# wifi_radio.net
KiCad netlist of a schematic drawn in Altium Designer
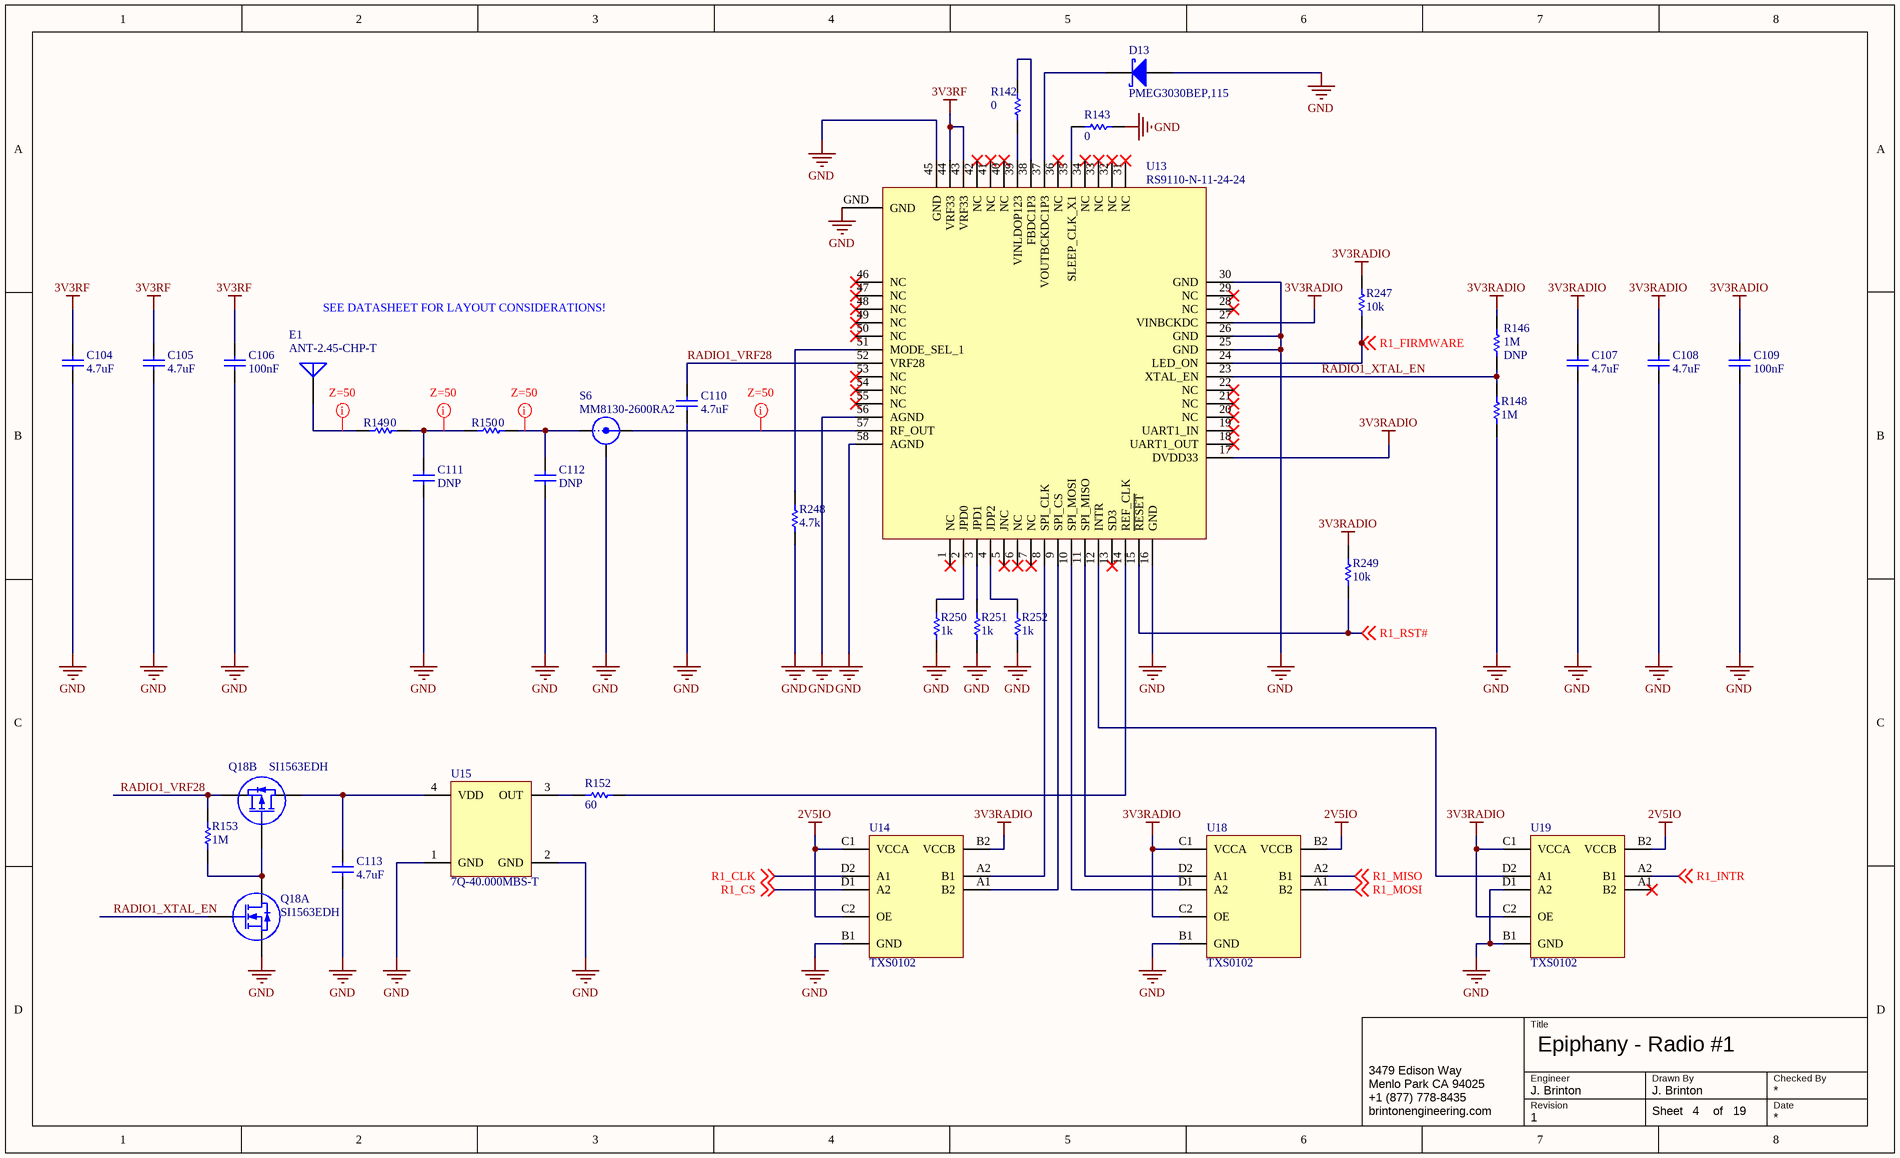
[diagram p0: wifi_radio.SchDoc]

(export (version "E")
  (design (tool "Eeschema 10.0.6"))
  (components
    (comp (ref "C104")
      (value "4.7uF")
      (footprint "0603")
      (description "Ceramic Capacitor 4.7uF +/-10% 6.3V SMD 0603")
      (fields (field (name "MANUFACTURER") "Kemet") (field (name "TOLERANCE") "+/-10%"))
      (libsource (lib "generic") (part "CAP"))
    )
    (comp (ref "C105")
      (value "4.7uF")
      (footprint "0603")
      (description "Ceramic Capacitor 4.7uF +/-10% 6.3V SMD 0603")
      (fields (field (name "MANUFACTURER") "Kemet") (field (name "TOLERANCE") "+/-10%"))
      (libsource (lib "generic") (part "CAP"))
    )
    (comp (ref "C106")
      (value "100nF")
      (footprint "0402")
      (description "Ceramic Capacitor 100nF +/-10% 16V X7R SMD 0402")
      (fields (field (name "MANUFACTURER") "Taiyo Yuden") (field (name "TOLERANCE") "+/-10%"))
      (libsource (lib "generic") (part "CAP"))
    )
    (comp (ref "C107")
      (value "4.7uF")
      (footprint "0603")
      (description "Ceramic Capacitor 4.7uF +/-10% 6.3V SMD 0603")
      (fields (field (name "MANUFACTURER") "Kemet") (field (name "TOLERANCE") "+/-10%"))
      (libsource (lib "generic") (part "CAP"))
    )
    (comp (ref "C108")
      (value "4.7uF")
      (footprint "0603")
      (description "Ceramic Capacitor 4.7uF +/-10% 6.3V SMD 0603")
      (fields (field (name "MANUFACTURER") "Kemet") (field (name "TOLERANCE") "+/-10%"))
      (libsource (lib "generic") (part "CAP"))
    )
    (comp (ref "C109")
      (value "100nF")
      (footprint "0402")
      (description "Ceramic Capacitor 100nF +/-10% 16V X7R SMD 0402")
      (fields (field (name "MANUFACTURER") "Taiyo Yuden") (field (name "TOLERANCE") "+/-10%"))
      (libsource (lib "generic") (part "CAP"))
    )
    (comp (ref "C110")
      (value "4.7uF")
      (footprint "0603")
      (description "Ceramic Capacitor 4.7uF +/-10% 6.3V SMD 0603")
      (fields (field (name "MANUFACTURER") "Kemet") (field (name "TOLERANCE") "+/-10%"))
      (libsource (lib "generic") (part "CAP"))
    )
    (comp (ref "C111")
      (value "CAP")
      (footprint "0201")
      (description "Ceramic Capacitor")
      (fields (field (name "DO NOT PLACE") "DNP"))
      (libsource (lib "generic") (part "CAP"))
    )
    (comp (ref "C112")
      (value "CAP")
      (footprint "0201")
      (description "Ceramic Capacitor")
      (fields (field (name "DO NOT PLACE") "DNP"))
      (libsource (lib "generic") (part "CAP"))
    )
    (comp (ref "C113")
      (value "4.7uF")
      (footprint "0603")
      (description "Ceramic Capacitor 4.7uF +/-10% 6.3V SMD 0603")
      (fields (field (name "MANUFACTURER") "Kemet") (field (name "TOLERANCE") "+/-10%"))
      (libsource (lib "generic") (part "CAP"))
    )
    (comp (ref "D13")
      (value "PMEG3030BEP,115")
      (footprint "PMEG3030BEP,115")
      (description "Schottky Diode 40V, 3A, SMD SOD-128")
      (fields
        (field (name "MANUFACTURER") "NXP Semiconductor")
        (field (name "MANUFACTURER P/N") "PMEG3030BEP,115")
      )
      (libsource (lib "generic") (part "SCHOTTKY"))
    )
    (comp (ref "E1")
      (value "ANT-2.45-CHP-T")
      (footprint "ANT-2.45-CHP-T")
      (description "Dielectric Chip Antenna 2.45GHz")
      (fields (field (name "MANUFACTURER") "Linx Technologies"))
      (libsource (lib "proto1") (part "ANT-2.45-CHP-T"))
    )
    (comp (ref "Q18")
      (value "SI1563EDH")
      (footprint "SI1563EDH")
      (description "Complementary Pair Enhancement Mode MOSFET")
      (fields (field (name "MANUFACTURER") "Vishay"))
      (libsource (lib "proto1") (part "SI1563EDH"))
    )
    (comp (ref "R142")
      (value "0")
      (footprint "0603")
      (description "Thick Film Chip Resistor 0 Ohms 1A SMD 0603")
      (fields (field (name "MANUFACTURER") "Panasonic - ECG") (field (name "Comment") "RES 0603 0 1A"))
      (libsource (lib "brinton") (part "RES"))
    )
    (comp (ref "R143")
      (value "0")
      (footprint "0603")
      (description "Thick Film Chip Resistor 0 Ohms 1A SMD 0603")
      (fields (field (name "MANUFACTURER") "Panasonic - ECG") (field (name "Comment") "RES 0603 0 1A"))
      (libsource (lib "brinton") (part "RES"))
    )
    (comp (ref "R146")
      (value "1M")
      (footprint "0603")
      (description "Thick Film Resistor 1M Ohms +/-1% 0.1W 75V SMD 0603")
      (fields
        (field (name "TOLERANCE") "+/-1%")
        (field (name "MANUFACTURER") "Panasonic - ECG")
        (field (name "DO NOT PLACE") "DNP")
      )
      (libsource (lib "brinton") (part "RES"))
    )
    (comp (ref "R148")
      (value "1M")
      (footprint "0603")
      (description "Thick Film Resistor 1M Ohms +/-1% 0.1W 75V SMD 0603")
      (fields (field (name "TOLERANCE") "+/-1%") (field (name "MANUFACTURER") "Panasonic - ECG"))
      (libsource (lib "brinton") (part "RES"))
    )
    (comp (ref "R149")
      (value "0")
      (footprint "0603")
      (description "Thick Film Chip Resistor 0 Ohms 1A SMD 0603")
      (fields (field (name "MANUFACTURER") "Panasonic - ECG") (field (name "Comment") "RES 0603 0 1A"))
      (libsource (lib "brinton") (part "RES"))
    )
    (comp (ref "R150")
      (value "0")
      (footprint "0603")
      (description "Thick Film Chip Resistor 0 Ohms 1A SMD 0603")
      (fields (field (name "MANUFACTURER") "Panasonic - ECG") (field (name "Comment") "RES 0603 0 1A"))
      (libsource (lib "brinton") (part "RES"))
    )
    (comp (ref "R152")
      (value "60")
      (footprint "0603")
      (description "Thick Film Chip Resistor 0 Ohms 1A SMD 0603")
      (fields (field (name "MANUFACTURER") "Panasonic - ECG") (field (name "Comment") "RES 0603 0 1A"))
      (libsource (lib "brinton") (part "RES"))
    )
    (comp (ref "R153")
      (value "1M")
      (footprint "0603")
      (description "Thick Film Resistor 1M Ohms +/-1% 0.1W 75V SMD 0603")
      (fields (field (name "TOLERANCE") "+/-1%") (field (name "MANUFACTURER") "Panasonic - ECG"))
      (libsource (lib "brinton") (part "RES"))
    )
    (comp (ref "R247")
      (value "10k")
      (footprint "0603")
      (description "Thick Film Resistor 10k Ohms +/-1% 0.1W 75V SMD 0603")
      (fields (field (name "TOLERANCE") "+/-1%") (field (name "MANUFACTURER") "Panasonic - ECG"))
      (libsource (lib "brinton") (part "RES"))
    )
    (comp (ref "R248")
      (value "4.7k")
      (footprint "0603")
      (description "Thick Film Resistor 4.7k Ohms +/-1% 0.1W 75V SMD 0603")
      (fields (field (name "TOLERANCE") "+/-1%") (field (name "MANUFACTURER") "Panasonic - ECG"))
      (libsource (lib "altium-import") (part "root_3_RES_"))
    )
    (comp (ref "R249")
      (value "10k")
      (footprint "0603")
      (description "Thick Film Resistor 10k Ohms +/-1% 0.1W 75V SMD 0603")
      (fields (field (name "TOLERANCE") "+/-1%") (field (name "MANUFACTURER") "Panasonic - ECG"))
      (libsource (lib "brinton") (part "RES"))
    )
    (comp (ref "R250")
      (value "1k")
      (footprint "0603")
      (description "Thick Film Resistor 1k Ohms +/-1% 0.1W 75V SMD 0603")
      (fields (field (name "TOLERANCE") "+/-1%") (field (name "MANUFACTURER") "Panasonic - ECG"))
      (libsource (lib "brinton") (part "RES"))
    )
    (comp (ref "R251")
      (value "1k")
      (footprint "0603")
      (description "Thick Film Resistor 1k Ohms +/-1% 0.1W 75V SMD 0603")
      (fields (field (name "TOLERANCE") "+/-1%") (field (name "MANUFACTURER") "Panasonic - ECG"))
      (libsource (lib "brinton") (part "RES"))
    )
    (comp (ref "R252")
      (value "1k")
      (footprint "0603")
      (description "Thick Film Resistor 1k Ohms +/-1% 0.1W 75V SMD 0603")
      (fields (field (name "TOLERANCE") "+/-1%") (field (name "MANUFACTURER") "Panasonic - ECG"))
      (libsource (lib "brinton") (part "RES"))
    )
    (comp (ref "S6")
      (value "MM8130-2600RA2")
      (footprint "MM8130-2600RA2")
      (description "Microwave Switch Connector")
      (fields (field (name "MANUFACTURER") "Murata"))
      (libsource (lib "proto1") (part "MM8130-2600RA2"))
    )
    (comp (ref "U13")
      (value "RS9110-N-11-24-24")
      (footprint "RS9110-N-11-24-24")
      (description "802.11bgn WLAN Module")
      (fields (field (name "MANUFACTURER") "Redpine Signals"))
      (libsource (lib "proto1") (part "RS9110-N-11-24"))
    )
    (comp (ref "U14")
      (value "TXS0102")
      (footprint "TXS0102YZPR")
      (description "Dual Bidirectional Digital Level Translator")
      (fields (field (name "MANUFACTURER") "Texas Instruments"))
      (libsource (lib "proto1") (part "TXS0102"))
    )
    (comp (ref "U15")
      (value "7Q-40.000MBS-T")
      (footprint "7Q-40.000MBS-T")
      (description "40MHz Crystal Clock Oscillator")
      (fields (field (name "MANUFACTURER") "TXC"))
      (libsource (lib "proto1") (part "7Q-40.000MBS-T"))
    )
    (comp (ref "U18")
      (value "TXS0102")
      (footprint "TXS0102YZPR")
      (description "Dual Bidirectional Digital Level Translator")
      (fields (field (name "MANUFACTURER") "Texas Instruments"))
      (libsource (lib "proto1") (part "TXS0102"))
    )
    (comp (ref "U19")
      (value "TXS0102")
      (footprint "TXS0102YZPR")
      (description "Dual Bidirectional Digital Level Translator")
      (fields (field (name "MANUFACTURER") "Texas Instruments"))
      (libsource (lib "proto1") (part "TXS0102"))
    )
  )
  (nets
    (net (code "1") (name "/RADIO1_VRF28") (class "Default")
      (node (ref "C110") (pin "2") (pinfunction "2_2") (pintype "passive"))
      (node (ref "Q18") (pin "4") (pinfunction "S_4") (pintype "passive"))
      (node (ref "R153") (pin "1") (pinfunction "1_1") (pintype "passive"))
      (node (ref "U13") (pin "52") (pinfunction "VRF28_52") (pintype "passive"))
    )
    (net (code "2") (name "/RADIO1_XTAL_EN") (class "Default")
      (node (ref "Q18") (pin "2") (pinfunction "G_2") (pintype "passive"))
      (node (ref "R146") (pin "2") (pinfunction "2_2") (pintype "passive"))
      (node (ref "R148") (pin "1") (pinfunction "1_1") (pintype "passive"))
      (node (ref "U13") (pin "23") (pinfunction "XTAL_EN_23") (pintype "passive"))
    )
    (net (code "3") (name "2V5IO") (class "Default")
      (node (ref "U14") (pin "C1") (pinfunction "VCCA_C1") (pintype "passive"))
      (node (ref "U14") (pin "C2") (pinfunction "OE_C2") (pintype "passive"))
      (node (ref "U18") (pin "B2") (pinfunction "VCCB_B2") (pintype "passive"))
      (node (ref "U19") (pin "B2") (pinfunction "VCCB_B2") (pintype "passive"))
    )
    (net (code "4") (name "3V3RADIO") (class "Default")
      (node (ref "C107") (pin "2") (pinfunction "2_2") (pintype "passive"))
      (node (ref "C108") (pin "2") (pinfunction "2_2") (pintype "passive"))
      (node (ref "C109") (pin "2") (pinfunction "2_2") (pintype "passive"))
      (node (ref "R146") (pin "1") (pinfunction "1_1") (pintype "passive"))
      (node (ref "R247") (pin "2") (pinfunction "2_2") (pintype "passive"))
      (node (ref "R249") (pin "2") (pinfunction "2_2") (pintype "passive"))
      (node (ref "U13") (pin "17") (pinfunction "DVDD33_17") (pintype "passive"))
      (node (ref "U13") (pin "27") (pinfunction "VINBCKDC_27") (pintype "passive"))
      (node (ref "U14") (pin "B2") (pinfunction "VCCB_B2") (pintype "passive"))
      (node (ref "U18") (pin "C1") (pinfunction "VCCA_C1") (pintype "passive"))
      (node (ref "U18") (pin "C2") (pinfunction "OE_C2") (pintype "passive"))
      (node (ref "U19") (pin "C1") (pinfunction "VCCA_C1") (pintype "passive"))
      (node (ref "U19") (pin "C2") (pinfunction "OE_C2") (pintype "passive"))
    )
    (net (code "5") (name "3V3RF") (class "Default")
      (node (ref "C104") (pin "2") (pinfunction "2_2") (pintype "passive"))
      (node (ref "C105") (pin "2") (pinfunction "2_2") (pintype "passive"))
      (node (ref "C106") (pin "2") (pinfunction "2_2") (pintype "passive"))
      (node (ref "U13") (pin "43") (pinfunction "VRF33_43") (pintype "passive"))
      (node (ref "U13") (pin "44") (pinfunction "VRF33_44") (pintype "passive"))
    )
    (net (code "6") (name "GND") (class "Default")
      (node (ref "C104") (pin "1") (pinfunction "1_1") (pintype "passive"))
      (node (ref "C105") (pin "1") (pinfunction "1_1") (pintype "passive"))
      (node (ref "C106") (pin "1") (pinfunction "1_1") (pintype "passive"))
      (node (ref "C107") (pin "1") (pinfunction "1_1") (pintype "passive"))
      (node (ref "C108") (pin "1") (pinfunction "1_1") (pintype "passive"))
      (node (ref "C109") (pin "1") (pinfunction "1_1") (pintype "passive"))
      (node (ref "C110") (pin "1") (pinfunction "1_1") (pintype "passive"))
      (node (ref "C111") (pin "1") (pinfunction "1_1") (pintype "passive"))
      (node (ref "C112") (pin "1") (pinfunction "1_1") (pintype "passive"))
      (node (ref "C113") (pin "1") (pinfunction "1_1") (pintype "passive"))
      (node (ref "D13") (pin "1") (pinfunction "A_1") (pintype "power_in"))
      (node (ref "Q18") (pin "1") (pinfunction "S_1") (pintype "passive"))
      (node (ref "R143") (pin "1") (pinfunction "1_1") (pintype "passive"))
      (node (ref "R148") (pin "2") (pinfunction "2_2") (pintype "passive"))
      (node (ref "R248") (pin "2") (pinfunction "2_2") (pintype "passive"))
      (node (ref "R250") (pin "2") (pinfunction "2_2") (pintype "passive"))
      (node (ref "R251") (pin "2") (pinfunction "2_2") (pintype "passive"))
      (node (ref "R252") (pin "2") (pinfunction "2_2") (pintype "passive"))
      (node (ref "S6") (pin "2") (pinfunction "GND_2") (pintype "passive"))
      (node (ref "U13") (pin "16") (pinfunction "GND_16") (pintype "passive"))
      (node (ref "U13") (pin "25") (pinfunction "GND_25") (pintype "passive"))
      (node (ref "U13") (pin "26") (pinfunction "GND_26") (pintype "passive"))
      (node (ref "U13") (pin "30") (pinfunction "GND_30") (pintype "passive"))
      (node (ref "U13") (pin "45") (pinfunction "GND_45") (pintype "passive"))
      (node (ref "U13") (pin "56") (pinfunction "AGND_56") (pintype "passive"))
      (node (ref "U13") (pin "58") (pinfunction "AGND_58") (pintype "passive"))
      (node (ref "U13") (pin "GND") (pinfunction "GND_GND") (pintype "passive"))
      (node (ref "U14") (pin "B1") (pinfunction "GND_B1") (pintype "passive"))
      (node (ref "U15") (pin "1") (pinfunction "GND_1") (pintype "passive"))
      (node (ref "U15") (pin "2") (pinfunction "GND_2") (pintype "passive"))
      (node (ref "U18") (pin "B1") (pinfunction "GND_B1") (pintype "passive"))
      (node (ref "U19") (pin "B1") (pinfunction "GND_B1") (pintype "passive"))
      (node (ref "U19") (pin "D1") (pinfunction "A2_D1") (pintype "passive"))
    )
    (net (code "7") (name "Net-(C111-Pad2)") (class "Default")
      (node (ref "C111") (pin "2") (pinfunction "2_2") (pintype "passive"))
      (node (ref "R149") (pin "2") (pinfunction "2_2") (pintype "passive"))
      (node (ref "R150") (pin "1") (pinfunction "1_1") (pintype "passive"))
    )
    (net (code "8") (name "Net-(D13-K)") (class "Default")
      (node (ref "D13") (pin "2") (pinfunction "K_2") (pintype "passive"))
      (node (ref "U13") (pin "37") (pinfunction "VOUTBCKDC1P3_37") (pintype "passive"))
    )
    (net (code "9") (name "Net-(E1-A)") (class "Default")
      (node (ref "E1") (pin "1") (pinfunction "A_1") (pintype "passive"))
      (node (ref "R149") (pin "1") (pinfunction "1_1") (pintype "passive"))
    )
    (net (code "10") (name "Net-(Q18A-D)") (class "Default")
      (node (ref "Q18") (pin "5") (pinfunction "G_5") (pintype "passive"))
      (node (ref "Q18") (pin "6") (pinfunction "D_6") (pintype "passive"))
      (node (ref "R153") (pin "2") (pinfunction "2_2") (pintype "passive"))
    )
    (net (code "11") (name "Net-(Q18B-D)") (class "Default")
      (node (ref "C113") (pin "2") (pinfunction "2_2") (pintype "passive"))
      (node (ref "Q18") (pin "3") (pinfunction "D_3") (pintype "passive"))
      (node (ref "U15") (pin "4") (pinfunction "VDD_4") (pintype "passive"))
    )
    (net (code "12") (name "Net-(S6-IN)") (class "Default")
      (node (ref "S6") (pin "1") (pinfunction "IN_1") (pintype "passive"))
      (node (ref "U13") (pin "57") (pinfunction "RF_OUT_57") (pintype "passive"))
    )
    (net (code "13") (name "Net-(S6-OUT)") (class "Default")
      (node (ref "C112") (pin "2") (pinfunction "2_2") (pintype "passive"))
      (node (ref "R150") (pin "2") (pinfunction "2_2") (pintype "passive"))
      (node (ref "S6") (pin "3") (pinfunction "OUT_3") (pintype "passive"))
    )
    (net (code "14") (name "Net-(U13-FBDC1P3)") (class "Default")
      (node (ref "R142") (pin "2") (pinfunction "2_2") (pintype "passive"))
      (node (ref "U13") (pin "38") (pinfunction "FBDC1P3_38") (pintype "passive"))
    )
    (net (code "15") (name "Net-(U13-INTR)") (class "Default")
      (node (ref "U13") (pin "12") (pinfunction "INTR_12") (pintype "passive"))
      (node (ref "U19") (pin "D2") (pinfunction "A1_D2") (pintype "passive"))
    )
    (net (code "16") (name "Net-(U13-JDP2)") (class "Default")
      (node (ref "R252") (pin "1") (pinfunction "1_1") (pintype "passive"))
      (node (ref "U13") (pin "4") (pinfunction "JDP2_4") (pintype "passive"))
    )
    (net (code "17") (name "Net-(U13-JPD0)") (class "Default")
      (node (ref "R250") (pin "1") (pinfunction "1_1") (pintype "passive"))
      (node (ref "U13") (pin "2") (pinfunction "JPD0_2") (pintype "passive"))
    )
    (net (code "18") (name "Net-(U13-JPD1)") (class "Default")
      (node (ref "R251") (pin "1") (pinfunction "1_1") (pintype "passive"))
      (node (ref "U13") (pin "3") (pinfunction "JPD1_3") (pintype "passive"))
    )
    (net (code "19") (name "Net-(U13-MODE_SEL_1)") (class "Default")
      (node (ref "R248") (pin "1") (pinfunction "1_1") (pintype "passive"))
      (node (ref "U13") (pin "51") (pinfunction "MODE_SEL_1_51") (pintype "passive"))
    )
    (net (code "20") (name "Net-(U13-REF_CLK)") (class "Default")
      (node (ref "R152") (pin "1") (pinfunction "1_1") (pintype "passive"))
      (node (ref "U13") (pin "14") (pinfunction "REF_CLK_14") (pintype "passive"))
    )
    (net (code "21") (name "Net-(U13-SLEEP_CLK_X1)") (class "Default")
      (node (ref "R143") (pin "2") (pinfunction "2_2") (pintype "passive"))
      (node (ref "U13") (pin "35") (pinfunction "SLEEP_CLK_X1_35") (pintype "passive"))
    )
    (net (code "22") (name "Net-(U13-SPI_CLK)") (class "Default")
      (node (ref "U13") (pin "8") (pinfunction "SPI_CLK_8") (pintype "passive"))
      (node (ref "U14") (pin "A2") (pinfunction "B1_A2") (pintype "passive"))
    )
    (net (code "23") (name "Net-(U13-SPI_CS)") (class "Default")
      (node (ref "U13") (pin "9") (pinfunction "SPI_CS_9") (pintype "passive"))
      (node (ref "U14") (pin "A1") (pinfunction "B2_A1") (pintype "passive"))
    )
    (net (code "24") (name "Net-(U13-SPI_MISO)") (class "Default")
      (node (ref "U13") (pin "11") (pinfunction "SPI_MISO_11") (pintype "passive"))
      (node (ref "U18") (pin "D2") (pinfunction "A1_D2") (pintype "passive"))
    )
    (net (code "25") (name "Net-(U13-SPI_MOSI)") (class "Default")
      (node (ref "U13") (pin "10") (pinfunction "SPI_MOSI_10") (pintype "passive"))
      (node (ref "U18") (pin "D1") (pinfunction "A2_D1") (pintype "passive"))
    )
    (net (code "26") (name "Net-(U13-VINLDOP123)") (class "Default")
      (node (ref "R142") (pin "1") (pinfunction "1_1") (pintype "passive"))
      (node (ref "U13") (pin "39") (pinfunction "VINLDOP123_39") (pintype "passive"))
    )
    (net (code "27") (name "Net-(U15-OUT)") (class "Default")
      (node (ref "R152") (pin "2") (pinfunction "2_2") (pintype "passive"))
      (node (ref "U15") (pin "3") (pinfunction "OUT_3") (pintype "passive"))
    )
    (net (code "28") (name "R1_CLK") (class "Default")
      (node (ref "U14") (pin "D2") (pinfunction "A1_D2") (pintype "passive"))
    )
    (net (code "29") (name "R1_CS") (class "Default")
      (node (ref "U14") (pin "D1") (pinfunction "A2_D1") (pintype "passive"))
    )
    (net (code "30") (name "R1_FIRMWARE") (class "Default")
      (node (ref "R247") (pin "1") (pinfunction "1_1") (pintype "passive"))
      (node (ref "U13") (pin "24") (pinfunction "LED_ON_24") (pintype "passive"))
    )
    (net (code "31") (name "R1_INTR") (class "Default")
      (node (ref "U19") (pin "A2") (pinfunction "B1_A2") (pintype "passive"))
    )
    (net (code "32") (name "R1_MISO") (class "Default")
      (node (ref "U18") (pin "A2") (pinfunction "B1_A2") (pintype "passive"))
    )
    (net (code "33") (name "R1_MOSI") (class "Default")
      (node (ref "U18") (pin "A1") (pinfunction "B2_A1") (pintype "passive"))
    )
    (net (code "34") (name "R1_RST#") (class "Default")
      (node (ref "R249") (pin "1") (pinfunction "1_1") (pintype "passive"))
      (node (ref "U13") (pin "15") (pinfunction "RESET_15") (pintype "passive"))
    )
    (net (code "35") (name "unconnected-(U13-JNC-Pad5)") (class "Default")
      (node (ref "U13") (pin "5") (pinfunction "JNC_5") (pintype "passive+no_connect"))
    )
    (net (code "36") (name "unconnected-(U13-NC-Pad1)") (class "Default")
      (node (ref "U13") (pin "1") (pinfunction "NC_1") (pintype "passive+no_connect"))
    )
    (net (code "37") (name "unconnected-(U13-NC-Pad6)") (class "Default")
      (node (ref "U13") (pin "6") (pinfunction "NC_6") (pintype "passive+no_connect"))
    )
    (net (code "38") (name "unconnected-(U13-NC-Pad7)") (class "Default")
      (node (ref "U13") (pin "7") (pinfunction "NC_7") (pintype "passive+no_connect"))
    )
    (net (code "39") (name "unconnected-(U13-NC-Pad20)") (class "Default")
      (node (ref "U13") (pin "20") (pinfunction "NC_20") (pintype "passive+no_connect"))
    )
    (net (code "40") (name "unconnected-(U13-NC-Pad21)") (class "Default")
      (node (ref "U13") (pin "21") (pinfunction "NC_21") (pintype "passive+no_connect"))
    )
    (net (code "41") (name "unconnected-(U13-NC-Pad22)") (class "Default")
      (node (ref "U13") (pin "22") (pinfunction "NC_22") (pintype "passive+no_connect"))
    )
    (net (code "42") (name "unconnected-(U13-NC-Pad28)") (class "Default")
      (node (ref "U13") (pin "28") (pinfunction "NC_28") (pintype "passive+no_connect"))
    )
    (net (code "43") (name "unconnected-(U13-NC-Pad29)") (class "Default")
      (node (ref "U13") (pin "29") (pinfunction "NC_29") (pintype "passive+no_connect"))
    )
    (net (code "44") (name "unconnected-(U13-NC-Pad31)") (class "Default")
      (node (ref "U13") (pin "31") (pinfunction "NC_31") (pintype "passive+no_connect"))
    )
    (net (code "45") (name "unconnected-(U13-NC-Pad32)") (class "Default")
      (node (ref "U13") (pin "32") (pinfunction "NC_32") (pintype "passive+no_connect"))
    )
    (net (code "46") (name "unconnected-(U13-NC-Pad33)") (class "Default")
      (node (ref "U13") (pin "33") (pinfunction "NC_33") (pintype "passive+no_connect"))
    )
    (net (code "47") (name "unconnected-(U13-NC-Pad34)") (class "Default")
      (node (ref "U13") (pin "34") (pinfunction "NC_34") (pintype "passive+no_connect"))
    )
    (net (code "48") (name "unconnected-(U13-NC-Pad36)") (class "Default")
      (node (ref "U13") (pin "36") (pinfunction "NC_36") (pintype "passive+no_connect"))
    )
    (net (code "49") (name "unconnected-(U13-NC-Pad40)") (class "Default")
      (node (ref "U13") (pin "40") (pinfunction "NC_40") (pintype "passive+no_connect"))
    )
    (net (code "50") (name "unconnected-(U13-NC-Pad41)") (class "Default")
      (node (ref "U13") (pin "41") (pinfunction "NC_41") (pintype "passive+no_connect"))
    )
    (net (code "51") (name "unconnected-(U13-NC-Pad42)") (class "Default")
      (node (ref "U13") (pin "42") (pinfunction "NC_42") (pintype "passive+no_connect"))
    )
    (net (code "52") (name "unconnected-(U13-NC-Pad46)") (class "Default")
      (node (ref "U13") (pin "46") (pinfunction "NC_46") (pintype "passive+no_connect"))
    )
    (net (code "53") (name "unconnected-(U13-NC-Pad47)") (class "Default")
      (node (ref "U13") (pin "47") (pinfunction "NC_47") (pintype "passive+no_connect"))
    )
    (net (code "54") (name "unconnected-(U13-NC-Pad48)") (class "Default")
      (node (ref "U13") (pin "48") (pinfunction "NC_48") (pintype "passive+no_connect"))
    )
    (net (code "55") (name "unconnected-(U13-NC-Pad49)") (class "Default")
      (node (ref "U13") (pin "49") (pinfunction "NC_49") (pintype "passive+no_connect"))
    )
    (net (code "56") (name "unconnected-(U13-NC-Pad50)") (class "Default")
      (node (ref "U13") (pin "50") (pinfunction "NC_50") (pintype "passive+no_connect"))
    )
    (net (code "57") (name "unconnected-(U13-NC-Pad53)") (class "Default")
      (node (ref "U13") (pin "53") (pinfunction "NC_53") (pintype "passive+no_connect"))
    )
    (net (code "58") (name "unconnected-(U13-NC-Pad54)") (class "Default")
      (node (ref "U13") (pin "54") (pinfunction "NC_54") (pintype "passive+no_connect"))
    )
    (net (code "59") (name "unconnected-(U13-NC-Pad55)") (class "Default")
      (node (ref "U13") (pin "55") (pinfunction "NC_55") (pintype "passive+no_connect"))
    )
    (net (code "60") (name "unconnected-(U13-SD3-Pad13)") (class "Default")
      (node (ref "U13") (pin "13") (pinfunction "SD3_13") (pintype "passive+no_connect"))
    )
    (net (code "61") (name "unconnected-(U13-UART1_IN-Pad19)") (class "Default")
      (node (ref "U13") (pin "19") (pinfunction "UART1_IN_19") (pintype "passive+no_connect"))
    )
    (net (code "62") (name "unconnected-(U13-UART1_OUT-Pad18)") (class "Default")
      (node (ref "U13") (pin "18") (pinfunction "UART1_OUT_18") (pintype "passive+no_connect"))
    )
    (net (code "63") (name "unconnected-(U19-B2-PadA1)") (class "Default")
      (node (ref "U19") (pin "A1") (pinfunction "B2_A1") (pintype "passive+no_connect"))
    )
  )
)
